# schematic.net
KiCad netlist of a schematic drawn in Altium Designer
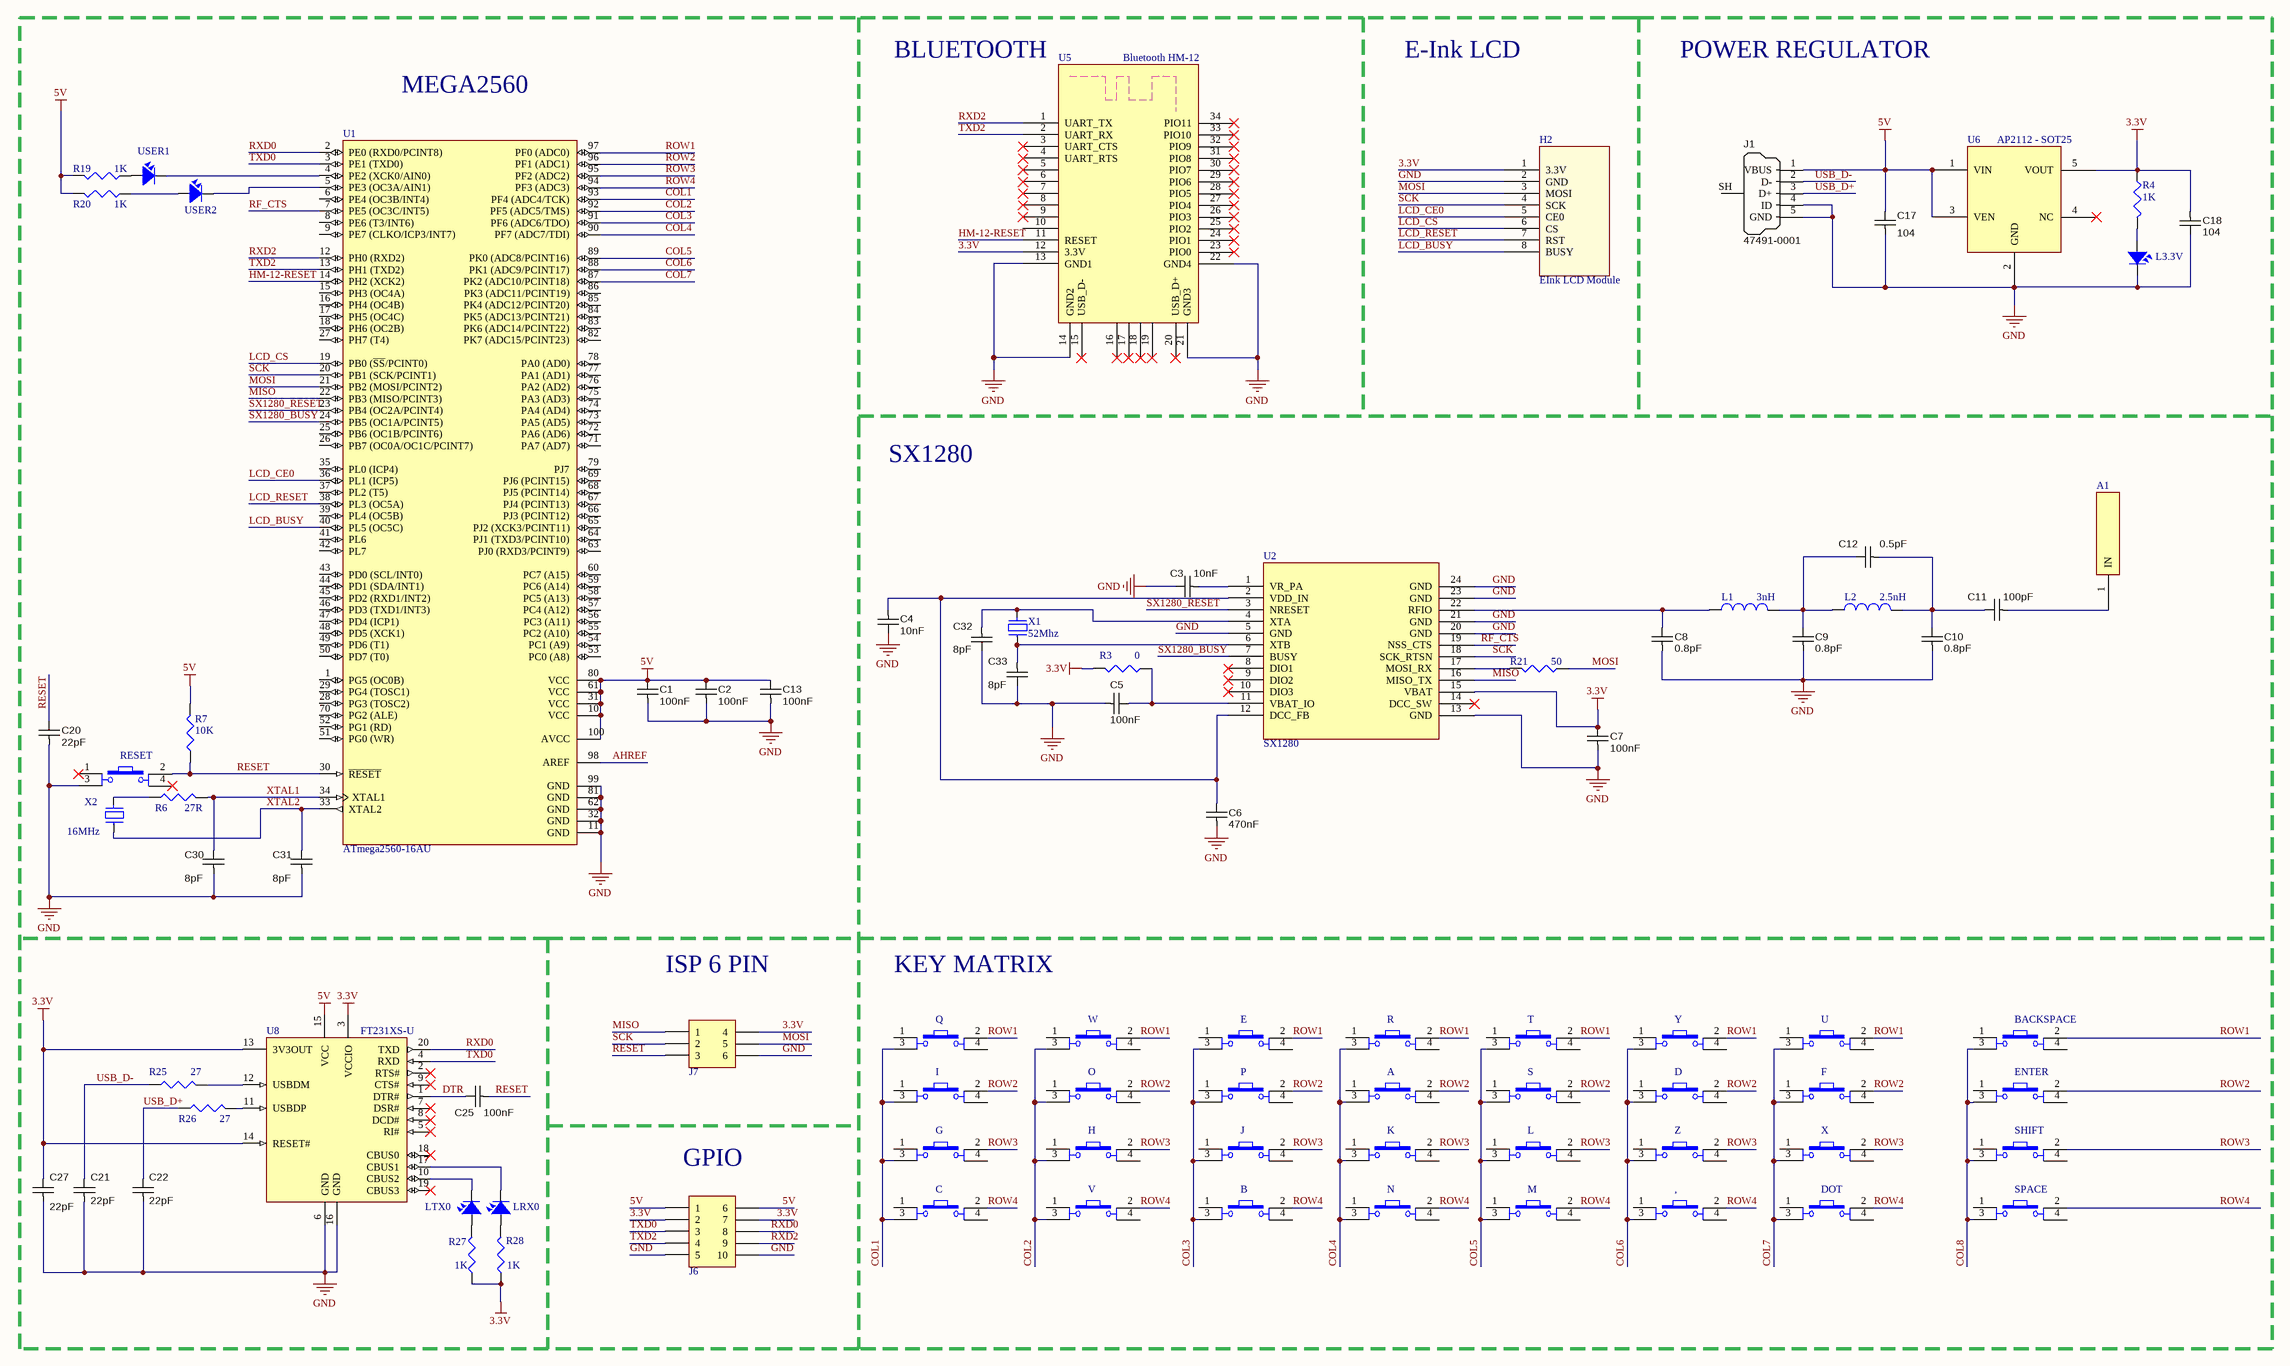
[diagram p0: schematic.SchDoc]

(export (version "E")
  (design (tool "Eeschema 10.0.6"))
  (components
    (comp (ref ",")
      (value "SW")
      (footprint "Kha_Button")
      (description "Switch button 4 pin")
      (libsource (lib "syhaunguyen") (part "SW4"))
    )
    (comp (ref "A")
      (value "SW")
      (footprint "Kha_Button")
      (description "Switch button 4 pin")
      (libsource (lib "syhaunguyen") (part "SW4"))
    )
    (comp (ref "A1")
      (value "Antenna")
      (footprint "Antenna")
      (libsource (lib "EInk_Project_Lib") (part "Antenna"))
    )
    (comp (ref "B")
      (value "SW")
      (footprint "Kha_Button")
      (description "Switch button 4 pin")
      (libsource (lib "syhaunguyen") (part "SW4"))
    )
    (comp (ref "BACKSPACE")
      (value "SW")
      (footprint "Kha_Button")
      (description "Switch button 4 pin")
      (libsource (lib "syhaunguyen") (part "SW4"))
    )
    (comp (ref "C")
      (value "SW")
      (footprint "Kha_Button")
      (description "Switch button 4 pin")
      (libsource (lib "syhaunguyen") (part "SW4"))
    )
    (comp (ref "C1")
      (value "100nF")
      (footprint "SMD-0603c")
      (description "Capacitor SMD Cer 1nF 10% 100V X7R 0603")
      (fields (field (name "TOLERANCE") "±10%") (field (name "Comment") "approved sub OK"))
      (libsource (lib "PBL - Capacitors") (part "CAPC_1n_0603_X7R_100V_10%"))
    )
    (comp (ref "C2")
      (value "100nF")
      (footprint "SMD-0603c")
      (description "Capacitor SMD Cer 1nF 10% 100V X7R 0603")
      (fields (field (name "TOLERANCE") "±10%") (field (name "Comment") "approved sub OK"))
      (libsource (lib "PBL - Capacitors") (part "CAPC_1n_0603_X7R_100V_10%"))
    )
    (comp (ref "C3")
      (value "10nF")
      (footprint "SMD-0603c")
      (description "Capacitor SMD Cer 1nF 10% 100V X7R 0603")
      (fields (field (name "TOLERANCE") "±10%") (field (name "Comment") "approved sub OK"))
      (libsource (lib "PBL - Capacitors") (part "CAPC_1n_0603_X7R_100V_10%"))
    )
    (comp (ref "C4")
      (value "10nF")
      (footprint "SMD-0603c")
      (description "Capacitor SMD Cer 1nF 10% 100V X7R 0603")
      (fields (field (name "TOLERANCE") "±10%") (field (name "Comment") "approved sub OK"))
      (libsource (lib "PBL - Capacitors") (part "CAPC_1n_0603_X7R_100V_10%"))
    )
    (comp (ref "C5")
      (value "100nF")
      (footprint "SMD-0603c")
      (description "Capacitor SMD Cer 1nF 10% 100V X7R 0603")
      (fields (field (name "TOLERANCE") "±10%") (field (name "Comment") "approved sub OK"))
      (libsource (lib "PBL - Capacitors") (part "CAPC_1n_0603_X7R_100V_10%"))
    )
    (comp (ref "C6")
      (value "470nF")
      (footprint "SMD-0603c")
      (description "Capacitor SMD Cer 1nF 10% 100V X7R 0603")
      (fields (field (name "TOLERANCE") "±10%") (field (name "Comment") "approved sub OK"))
      (libsource (lib "PBL - Capacitors") (part "CAPC_1n_0603_X7R_100V_10%"))
    )
    (comp (ref "C7")
      (value "100nF")
      (footprint "SMD-0603c")
      (description "Capacitor SMD Cer 1nF 10% 100V X7R 0603")
      (fields (field (name "TOLERANCE") "±10%") (field (name "Comment") "approved sub OK"))
      (libsource (lib "PBL - Capacitors") (part "CAPC_1n_0603_X7R_100V_10%"))
    )
    (comp (ref "C8")
      (value "0.8pF")
      (footprint "SMD-0603c")
      (description "Capacitor SMD Cer 1nF 10% 100V X7R 0603")
      (fields (field (name "TOLERANCE") "±10%") (field (name "Comment") "approved sub OK"))
      (libsource (lib "PBL - Capacitors") (part "CAPC_1n_0603_X7R_100V_10%"))
    )
    (comp (ref "C9")
      (value "0.8pF")
      (footprint "SMD-0603c")
      (description "Capacitor SMD Cer 1nF 10% 100V X7R 0603")
      (fields (field (name "TOLERANCE") "±10%") (field (name "Comment") "approved sub OK"))
      (libsource (lib "PBL - Capacitors") (part "CAPC_1n_0603_X7R_100V_10%"))
    )
    (comp (ref "C10")
      (value "0.8pF")
      (footprint "SMD-0603c")
      (description "Capacitor SMD Cer 1nF 10% 100V X7R 0603")
      (fields (field (name "TOLERANCE") "±10%") (field (name "Comment") "approved sub OK"))
      (libsource (lib "PBL - Capacitors") (part "CAPC_1n_0603_X7R_100V_10%"))
    )
    (comp (ref "C11")
      (value "100pF")
      (footprint "SMD-0603c")
      (description "Capacitor SMD Cer 1nF 10% 100V X7R 0603")
      (fields (field (name "TOLERANCE") "±10%") (field (name "Comment") "approved sub OK"))
      (libsource (lib "PBL - Capacitors") (part "CAPC_1n_0603_X7R_100V_10%"))
    )
    (comp (ref "C12")
      (value "0.5pF")
      (footprint "SMD-0603c")
      (description "Capacitor SMD Cer 1nF 10% 100V X7R 0603")
      (fields (field (name "TOLERANCE") "±10%") (field (name "Comment") "approved sub OK"))
      (libsource (lib "PBL - Capacitors") (part "CAPC_1n_0603_X7R_100V_10%"))
    )
    (comp (ref "C13")
      (value "100nF")
      (footprint "SMD-0603c")
      (description "Capacitor SMD Cer 1nF 10% 100V X7R 0603")
      (fields (field (name "TOLERANCE") "±10%") (field (name "Comment") "approved sub OK"))
      (libsource (lib "PBL - Capacitors") (part "CAPC_1n_0603_X7R_100V_10%"))
    )
    (comp (ref "C17")
      (value "104")
      (footprint "SMD-0603c")
      (description "Capacitor SMD Cer 1nF 10% 100V X7R 0603")
      (fields (field (name "TOLERANCE") "±10%") (field (name "Comment") "approved sub OK"))
      (libsource (lib "PBL - Capacitors") (part "CAPC_1n_0603_X7R_100V_10%"))
    )
    (comp (ref "C18")
      (value "104")
      (footprint "SMD-0603c")
      (description "Capacitor SMD Cer 1nF 10% 100V X7R 0603")
      (fields (field (name "TOLERANCE") "±10%") (field (name "Comment") "approved sub OK"))
      (libsource (lib "PBL - Capacitors") (part "CAPC_1n_0603_X7R_100V_10%"))
    )
    (comp (ref "C20")
      (value "22pF")
      (footprint "SMD-0603c")
      (description "Capacitor SMD Cer 1nF 10% 100V X7R 0603")
      (fields (field (name "TOLERANCE") "±10%") (field (name "Comment") "approved sub OK"))
      (libsource (lib "PBL - Capacitors") (part "CAPC_1n_0603_X7R_100V_10%"))
    )
    (comp (ref "C21")
      (value "22pF")
      (footprint "SMD-0603c")
      (description "Capacitor SMD Cer 1nF 10% 100V X7R 0603")
      (fields (field (name "TOLERANCE") "±10%") (field (name "Comment") "approved sub OK"))
      (libsource (lib "PBL - Capacitors") (part "CAPC_1n_0603_X7R_100V_10%"))
    )
    (comp (ref "C22")
      (value "22pF")
      (footprint "SMD-0603c")
      (description "Capacitor SMD Cer 1nF 10% 100V X7R 0603")
      (fields (field (name "TOLERANCE") "±10%") (field (name "Comment") "approved sub OK"))
      (libsource (lib "PBL - Capacitors") (part "CAPC_1n_0603_X7R_100V_10%"))
    )
    (comp (ref "C25")
      (value "100nF")
      (footprint "SMD-0603c")
      (description "Capacitor SMD Cer 1nF 10% 100V X7R 0603")
      (fields (field (name "TOLERANCE") "±10%") (field (name "Comment") "approved sub OK"))
      (libsource (lib "PBL - Capacitors") (part "CAPC_1n_0603_X7R_100V_10%"))
    )
    (comp (ref "C27")
      (value "22pF")
      (footprint "SMD-0603c")
      (description "Capacitor SMD Cer 1nF 10% 100V X7R 0603")
      (fields (field (name "TOLERANCE") "±10%") (field (name "Comment") "approved sub OK"))
      (libsource (lib "PBL - Capacitors") (part "CAPC_1n_0603_X7R_100V_10%"))
    )
    (comp (ref "C30")
      (value "8pF")
      (footprint "SMD-0603c")
      (description "Capacitor SMD Cer 1nF 10% 100V X7R 0603")
      (fields (field (name "TOLERANCE") "±10%") (field (name "Comment") "approved sub OK"))
      (libsource (lib "PBL - Capacitors") (part "CAPC_1n_0603_X7R_100V_10%"))
    )
    (comp (ref "C31")
      (value "8pF")
      (footprint "SMD-0603c")
      (description "Capacitor SMD Cer 1nF 10% 100V X7R 0603")
      (fields (field (name "TOLERANCE") "±10%") (field (name "Comment") "approved sub OK"))
      (libsource (lib "PBL - Capacitors") (part "CAPC_1n_0603_X7R_100V_10%"))
    )
    (comp (ref "C32")
      (value "8pF")
      (footprint "SMD-0603c")
      (description "Capacitor SMD Cer 1nF 10% 100V X7R 0603")
      (fields (field (name "TOLERANCE") "±10%") (field (name "Comment") "approved sub OK"))
      (libsource (lib "PBL - Capacitors") (part "CAPC_1n_0603_X7R_100V_10%"))
    )
    (comp (ref "C33")
      (value "8pF")
      (footprint "SMD-0603c")
      (description "Capacitor SMD Cer 1nF 10% 100V X7R 0603")
      (fields (field (name "TOLERANCE") "±10%") (field (name "Comment") "approved sub OK"))
      (libsource (lib "PBL - Capacitors") (part "CAPC_1n_0603_X7R_100V_10%"))
    )
    (comp (ref "D")
      (value "SW")
      (footprint "Kha_Button")
      (description "Switch button 4 pin")
      (libsource (lib "syhaunguyen") (part "SW4"))
    )
    (comp (ref "DOT")
      (value "SW")
      (footprint "Kha_Button")
      (description "Switch button 4 pin")
      (libsource (lib "syhaunguyen") (part "SW4"))
    )
    (comp (ref "E")
      (value "SW")
      (footprint "Kha_Button")
      (description "Switch button 4 pin")
      (libsource (lib "syhaunguyen") (part "SW4"))
    )
    (comp (ref "ENTER")
      (value "SW")
      (footprint "Kha_Button")
      (description "Switch button 4 pin")
      (libsource (lib "syhaunguyen") (part "SW4"))
    )
    (comp (ref "F")
      (value "SW")
      (footprint "Kha_Button")
      (description "Switch button 4 pin")
      (libsource (lib "syhaunguyen") (part "SW4"))
    )
    (comp (ref "G")
      (value "SW")
      (footprint "Kha_Button")
      (description "Switch button 4 pin")
      (libsource (lib "syhaunguyen") (part "SW4"))
    )
    (comp (ref "H")
      (value "SW")
      (footprint "Kha_Button")
      (description "Switch button 4 pin")
      (libsource (lib "syhaunguyen") (part "SW4"))
    )
    (comp (ref "H2")
      (value "EInk LCD Module")
      (footprint "EInk_Module")
      (libsource (lib "EInk_Project_Lib") (part "E-Ink LCD"))
    )
    (comp (ref "I")
      (value "SW")
      (footprint "Kha_Button")
      (description "Switch button 4 pin")
      (libsource (lib "syhaunguyen") (part "SW4"))
    )
    (comp (ref "J")
      (value "SW")
      (footprint "Kha_Button")
      (description "Switch button 4 pin")
      (libsource (lib "syhaunguyen") (part "SW4"))
    )
    (comp (ref "J1")
      (value "USB Micro Type B")
      (footprint "ZIF_CONN_4P_TE84953-4")
      (description "Connector SMD USB Micro Type B middle mount")
      (fields (field (name "MANUFACTURER PART NUMBER 1") "47491-0001"))
      (libsource (lib "PBL - Connectors") (part "USB_Micro_TypeB"))
    )
    (comp (ref "J6")
      (value "10p")
      (footprint "610110249121")
      (description "WR-PHD 2.54 mm Pin Header - SMT Type Double Row Right Angled, 10p")
      (fields (field (name "PARTNUMBER") "610110249121") (field (name "PUBLISHER") "Wurth Elektronik"))
      (libsource (lib "ALTIUM-PHD_2_54_SMT_DOUBLE_ROW_RIGHT_ANGLED_PIN_HEADER_6101XX249121-rev16c") (part "610110249121"))
    )
    (comp (ref "J7")
      (value "06p")
      (footprint "610106249121")
      (description "WR-PHD 2.54 mm Pin Header - SMT Type Double Row Right Angled, 06p")
      (fields (field (name "PARTNUMBER") "610106249121") (field (name "PUBLISHER") "Wurth Elektronik"))
      (libsource (lib "ALTIUM-PHD_2_54_SMT_DOUBLE_ROW_RIGHT_ANGLED_PIN_HEADER_6101XX249121-rev16c") (part "610106249121"))
    )
    (comp (ref "K")
      (value "SW")
      (footprint "Kha_Button")
      (description "Switch button 4 pin")
      (libsource (lib "syhaunguyen") (part "SW4"))
    )
    (comp (ref "L")
      (value "SW")
      (footprint "Kha_Button")
      (description "Switch button 4 pin")
      (libsource (lib "syhaunguyen") (part "SW4"))
    )
    (comp (ref "L1")
      (value "3nH")
      (footprint "0603")
      (description "Inductor")
      (fields (field (name "PUBLISHER") "Altium Limited"))
      (libsource (lib "Miscellaneous Devices") (part "Inductor"))
    )
    (comp (ref "L2")
      (value "2.5nH")
      (footprint "0603")
      (description "Inductor")
      (fields (field (name "PUBLISHER") "Altium Limited"))
      (libsource (lib "Miscellaneous Devices") (part "Inductor"))
    )
    (comp (ref "L3.3V")
      (value "LED SMD")
      (footprint "SM-LED-0805-Blue")
      (libsource (lib "syhaunguyen") (part "LED-SMD-0805"))
    )
    (comp (ref "LRX0")
      (value "LED SMD")
      (footprint "SM-LED-0805-Blue")
      (libsource (lib "syhaunguyen") (part "LED-SMD-0805"))
    )
    (comp (ref "LTX0")
      (value "LED SMD")
      (footprint "SM-LED-0805-Blue")
      (libsource (lib "syhaunguyen") (part "LED-SMD-0805"))
    )
    (comp (ref "M")
      (value "SW")
      (footprint "Kha_Button")
      (description "Switch button 4 pin")
      (libsource (lib "syhaunguyen") (part "SW4"))
    )
    (comp (ref "N")
      (value "SW")
      (footprint "Kha_Button")
      (description "Switch button 4 pin")
      (libsource (lib "syhaunguyen") (part "SW4"))
    )
    (comp (ref "O")
      (value "SW")
      (footprint "Kha_Button")
      (description "Switch button 4 pin")
      (libsource (lib "syhaunguyen") (part "SW4"))
    )
    (comp (ref "P")
      (value "SW")
      (footprint "Kha_Button")
      (description "Switch button 4 pin")
      (libsource (lib "syhaunguyen") (part "SW4"))
    )
    (comp (ref "Q")
      (value "SW")
      (footprint "Kha_Button")
      (description "Switch button 4 pin")
      (libsource (lib "syhaunguyen") (part "SW4"))
    )
    (comp (ref "R")
      (value "SW")
      (footprint "Kha_Button")
      (description "Switch button 4 pin")
      (libsource (lib "syhaunguyen") (part "SW4"))
    )
    (comp (ref "R3")
      (value "0")
      (footprint "J1-0603")
      (description "Resistor")
      (fields (field (name "Comment") "Res3") (field (name "PUBLISHER") "Altium Limited"))
      (libsource (lib "Miscellaneous Devices") (part "Res3"))
    )
    (comp (ref "R4")
      (value "1K")
      (footprint "J1-0603")
      (description "Resistor")
      (fields (field (name "Comment") "Res3") (field (name "PUBLISHER") "Altium Limited"))
      (libsource (lib "Miscellaneous Devices") (part "Res3"))
    )
    (comp (ref "R6")
      (value "27R")
      (footprint "J1-0603")
      (description "Resistor")
      (fields (field (name "Comment") "Res3") (field (name "PUBLISHER") "Altium Limited"))
      (libsource (lib "Miscellaneous Devices") (part "Res3"))
    )
    (comp (ref "R7")
      (value "10K")
      (footprint "J1-0603")
      (description "Resistor")
      (fields (field (name "Comment") "Res3") (field (name "PUBLISHER") "Altium Limited"))
      (libsource (lib "Miscellaneous Devices") (part "Res3"))
    )
    (comp (ref "R19")
      (value "1K")
      (footprint "J1-0603")
      (description "Resistor")
      (fields (field (name "Comment") "Res3") (field (name "PUBLISHER") "Altium Limited"))
      (libsource (lib "Miscellaneous Devices") (part "Res3"))
    )
    (comp (ref "R20")
      (value "1K")
      (footprint "J1-0603")
      (description "Resistor")
      (fields (field (name "Comment") "Res3") (field (name "PUBLISHER") "Altium Limited"))
      (libsource (lib "Miscellaneous Devices") (part "Res3"))
    )
    (comp (ref "R21")
      (value "50")
      (footprint "J1-0603")
      (description "Resistor")
      (fields (field (name "Comment") "Res3") (field (name "PUBLISHER") "Altium Limited"))
      (libsource (lib "Miscellaneous Devices") (part "Res3"))
    )
    (comp (ref "R25")
      (value "27")
      (footprint "J1-0603")
      (description "Resistor")
      (fields (field (name "Comment") "Res3") (field (name "PUBLISHER") "Altium Limited"))
      (libsource (lib "Miscellaneous Devices") (part "Res3"))
    )
    (comp (ref "R26")
      (value "27")
      (footprint "J1-0603")
      (description "Resistor")
      (fields (field (name "Comment") "Res3") (field (name "PUBLISHER") "Altium Limited"))
      (libsource (lib "Miscellaneous Devices") (part "Res3"))
    )
    (comp (ref "R27")
      (value "1K")
      (footprint "J1-0603")
      (description "Resistor")
      (fields (field (name "Comment") "Res3") (field (name "PUBLISHER") "Altium Limited"))
      (libsource (lib "Miscellaneous Devices") (part "Res3"))
    )
    (comp (ref "R28")
      (value "1K")
      (footprint "J1-0603")
      (description "Resistor")
      (fields (field (name "Comment") "Res3") (field (name "PUBLISHER") "Altium Limited"))
      (libsource (lib "Miscellaneous Devices") (part "Res3"))
    )
    (comp (ref "RESET")
      (value "SW")
      (footprint "Kha_Button")
      (description "Switch button 4 pin")
      (libsource (lib "syhaunguyen") (part "SW4"))
    )
    (comp (ref "S")
      (value "SW")
      (footprint "Kha_Button")
      (description "Switch button 4 pin")
      (libsource (lib "syhaunguyen") (part "SW4"))
    )
    (comp (ref "SHIFT")
      (value "SW")
      (footprint "Kha_Button")
      (description "Switch button 4 pin")
      (libsource (lib "syhaunguyen") (part "SW4"))
    )
    (comp (ref "SPACE")
      (value "SW")
      (footprint "Kha_Button")
      (description "Switch button 4 pin")
      (libsource (lib "syhaunguyen") (part "SW4"))
    )
    (comp (ref "T")
      (value "SW")
      (footprint "Kha_Button")
      (description "Switch button 4 pin")
      (libsource (lib "syhaunguyen") (part "SW4"))
    )
    (comp (ref "U")
      (value "SW")
      (footprint "Kha_Button")
      (description "Switch button 4 pin")
      (libsource (lib "syhaunguyen") (part "SW4"))
    )
    (comp (ref "U1")
      (value "ATmega2560-16AU")
      (footprint "100A_N")
      (fields (field (name "PUBLISHER") "Altium Limited"))
      (libsource (lib "Atmel Microcontroller 8-Bit megaAVR") (part "ATmega2560-16AU"))
    )
    (comp (ref "U2")
      (value "SX1280")
      (footprint "SX1280_QFN24 4x4")
      (libsource (lib "EInk_Project_Lib") (part "SX1280"))
    )
    (comp (ref "U5")
      (value "Bluetooth HM-12")
      (footprint "HM-12")
      (libsource (lib "EInk_Project_Lib") (part "HM-12"))
    )
    (comp (ref "U6")
      (value "AP2112 - SOT25")
      (footprint "AP2112 - SOT25")
      (libsource (lib "EInk_Project_Lib") (part "AP2112 - SOT25"))
    )
    (comp (ref "U8")
      (value "FT231XS-U")
      (footprint "SSOP-20_N")
      (fields (field (name "MANUFACTURER") "FTDI"))
      (libsource (lib "FTDI FT-X Series") (part "FT231XS-U"))
    )
    (comp (ref "USER1")
      (value "LED SMD")
      (footprint "SM-LED-0805-Blue")
      (libsource (lib "syhaunguyen") (part "LED-SMD-0805"))
    )
    (comp (ref "USER2")
      (value "LED SMD")
      (footprint "SM-LED-0805-Blue")
      (libsource (lib "syhaunguyen") (part "LED-SMD-0805"))
    )
    (comp (ref "V")
      (value "SW")
      (footprint "Kha_Button")
      (description "Switch button 4 pin")
      (libsource (lib "syhaunguyen") (part "SW4"))
    )
    (comp (ref "W")
      (value "SW")
      (footprint "Kha_Button")
      (description "Switch button 4 pin")
      (libsource (lib "syhaunguyen") (part "SW4"))
    )
    (comp (ref "X")
      (value "SW")
      (footprint "Kha_Button")
      (description "Switch button 4 pin")
      (libsource (lib "syhaunguyen") (part "SW4"))
    )
    (comp (ref "X1")
      (value "52Mhz")
      (footprint "Crystal 52MHz")
      (description "Crystal For all Crystal 2pin.")
      (libsource (lib "syhaunguyen") (part "XT2"))
    )
    (comp (ref "X2")
      (value "16MHz")
      (footprint "PCBComponent_1")
      (description "Crystal For all Crystal 2pin.")
      (libsource (lib "") (part "XT2_1"))
    )
    (comp (ref "Y")
      (value "SW")
      (footprint "Kha_Button")
      (description "Switch button 4 pin")
      (libsource (lib "syhaunguyen") (part "SW4"))
    )
    (comp (ref "Z")
      (value "SW")
      (footprint "Kha_Button")
      (description "Switch button 4 pin")
      (libsource (lib "syhaunguyen") (part "SW4"))
    )
  )
  (nets
    (net (code "1") (name "/AHREF") (class "Default")
      (node (ref "U1") (pin "98") (pinfunction "AREF_98") (pintype "power_in"))
    )
    (net (code "2") (name "/COL1") (class "Default")
      (node (ref "C") (pin "3") (pintype "passive"))
      (node (ref "G") (pin "3") (pintype "passive"))
      (node (ref "I") (pin "3") (pintype "passive"))
      (node (ref "Q") (pin "3") (pintype "passive"))
      (node (ref "U1") (pin "93") (pinfunction "PF4_(ADC4/TCK)_93") (pintype "bidirectional"))
    )
    (net (code "3") (name "/COL2") (class "Default")
      (node (ref "H") (pin "3") (pintype "passive"))
      (node (ref "O") (pin "3") (pintype "passive"))
      (node (ref "U1") (pin "92") (pinfunction "PF5_(ADC5/TMS)_92") (pintype "bidirectional"))
      (node (ref "V") (pin "3") (pintype "passive"))
      (node (ref "W") (pin "3") (pintype "passive"))
    )
    (net (code "4") (name "/COL3") (class "Default")
      (node (ref "B") (pin "3") (pintype "passive"))
      (node (ref "E") (pin "3") (pintype "passive"))
      (node (ref "J") (pin "3") (pintype "passive"))
      (node (ref "P") (pin "3") (pintype "passive"))
      (node (ref "U1") (pin "91") (pinfunction "PF6_(ADC6/TDO)_91") (pintype "bidirectional"))
    )
    (net (code "5") (name "/COL4") (class "Default")
      (node (ref "A") (pin "3") (pintype "passive"))
      (node (ref "K") (pin "3") (pintype "passive"))
      (node (ref "N") (pin "3") (pintype "passive"))
      (node (ref "R") (pin "3") (pintype "passive"))
      (node (ref "U1") (pin "90") (pinfunction "PF7_(ADC7/TDI)_90") (pintype "bidirectional"))
    )
    (net (code "6") (name "/COL5") (class "Default")
      (node (ref "L") (pin "3") (pintype "passive"))
      (node (ref "M") (pin "3") (pintype "passive"))
      (node (ref "S") (pin "3") (pintype "passive"))
      (node (ref "T") (pin "3") (pintype "passive"))
      (node (ref "U1") (pin "89") (pinfunction "PK0_(ADC8/PCINT16)_89") (pintype "bidirectional"))
    )
    (net (code "7") (name "/COL6") (class "Default")
      (node (ref ",") (pin "3") (pintype "passive"))
      (node (ref "D") (pin "3") (pintype "passive"))
      (node (ref "U1") (pin "88") (pinfunction "PK1_(ADC9/PCINT17)_88") (pintype "bidirectional"))
      (node (ref "Y") (pin "3") (pintype "passive"))
      (node (ref "Z") (pin "3") (pintype "passive"))
    )
    (net (code "8") (name "/COL7") (class "Default")
      (node (ref "DOT") (pin "3") (pintype "passive"))
      (node (ref "F") (pin "3") (pintype "passive"))
      (node (ref "U") (pin "3") (pintype "passive"))
      (node (ref "U1") (pin "87") (pinfunction "PK2_(ADC10/PCINT18)_87") (pintype "bidirectional"))
      (node (ref "X") (pin "3") (pintype "passive"))
    )
    (net (code "9") (name "/COL8") (class "Default")
      (node (ref "BACKSPACE") (pin "3") (pintype "passive"))
      (node (ref "ENTER") (pin "3") (pintype "passive"))
      (node (ref "SHIFT") (pin "3") (pintype "passive"))
      (node (ref "SPACE") (pin "3") (pintype "passive"))
    )
    (net (code "10") (name "/DTR") (class "Default")
      (node (ref "C25") (pin "2") (pintype "passive"))
      (node (ref "U8") (pin "1") (pinfunction "DTR#_1") (pintype "output"))
    )
    (net (code "11") (name "/HM-12-RESET") (class "Default")
      (node (ref "U1") (pin "14") (pinfunction "PH2_(XCK2)_14") (pintype "bidirectional"))
      (node (ref "U5") (pin "11") (pinfunction "RESET_11") (pintype "passive"))
    )
    (net (code "12") (name "/LCD_BUSY") (class "Default")
      (node (ref "H2") (pin "8") (pinfunction "BUSY_8") (pintype "passive"))
      (node (ref "U1") (pin "40") (pinfunction "PL5_(OC5C)_40") (pintype "bidirectional"))
    )
    (net (code "13") (name "/LCD_CE0") (class "Default")
      (node (ref "H2") (pin "5") (pinfunction "CE0_5") (pintype "passive"))
      (node (ref "U1") (pin "36") (pinfunction "PL1_(ICP5)_36") (pintype "bidirectional"))
    )
    (net (code "14") (name "/LCD_CS") (class "Default")
      (node (ref "H2") (pin "6") (pinfunction "CS_6") (pintype "passive"))
      (node (ref "U1") (pin "19") (pinfunction "PB0_(~{SS}/PCINT0)_19") (pintype "bidirectional"))
    )
    (net (code "15") (name "/LCD_RESET") (class "Default")
      (node (ref "H2") (pin "7") (pinfunction "RST_7") (pintype "passive"))
      (node (ref "U1") (pin "38") (pinfunction "PL3_(OC5A)_38") (pintype "bidirectional"))
    )
    (net (code "16") (name "/MISO") (class "Default")
      (node (ref "J7") (pin "1") (pinfunction "1_1") (pintype "passive"))
      (node (ref "U1") (pin "22") (pinfunction "PB3_(MISO/PCINT3)_22") (pintype "bidirectional"))
      (node (ref "U2") (pin "16") (pinfunction "MISO_TX_16") (pintype "passive"))
    )
    (net (code "17") (name "/MOSI") (class "Default")
      (node (ref "H2") (pin "3") (pinfunction "MOSI_3") (pintype "passive"))
      (node (ref "J7") (pin "5") (pinfunction "5_5") (pintype "passive"))
      (node (ref "R21") (pin "1") (pinfunction "1_1") (pintype "passive"))
      (node (ref "U1") (pin "21") (pinfunction "PB2_(MOSI/PCINT2)_21") (pintype "bidirectional"))
    )
    (net (code "18") (name "/RESET") (class "Default")
      (node (ref "C20") (pin "2") (pintype "passive"))
      (node (ref "C25") (pin "1") (pintype "passive"))
      (node (ref "J7") (pin "3") (pinfunction "3_3") (pintype "passive"))
      (node (ref "R7") (pin "1") (pinfunction "1_1") (pintype "passive"))
      (node (ref "RESET") (pin "2") (pintype "passive"))
      (node (ref "U1") (pin "30") (pinfunction "~{RESET}_30") (pintype "input"))
    )
    (net (code "19") (name "/RF_CTS") (class "Default")
      (node (ref "U1") (pin "7") (pinfunction "PE5_(OC3C/INT5)_7") (pintype "bidirectional"))
      (node (ref "U2") (pin "19") (pinfunction "NSS_CTS_19") (pintype "passive"))
    )
    (net (code "20") (name "/ROW1") (class "Default")
      (node (ref "BACKSPACE") (pin "2") (pintype "passive"))
      (node (ref "E") (pin "2") (pintype "passive"))
      (node (ref "Q") (pin "2") (pintype "passive"))
      (node (ref "R") (pin "2") (pintype "passive"))
      (node (ref "T") (pin "2") (pintype "passive"))
      (node (ref "U") (pin "2") (pintype "passive"))
      (node (ref "U1") (pin "97") (pinfunction "PF0_(ADC0)_97") (pintype "bidirectional"))
      (node (ref "W") (pin "2") (pintype "passive"))
      (node (ref "Y") (pin "2") (pintype "passive"))
    )
    (net (code "21") (name "/ROW2") (class "Default")
      (node (ref "A") (pin "2") (pintype "passive"))
      (node (ref "D") (pin "2") (pintype "passive"))
      (node (ref "ENTER") (pin "2") (pintype "passive"))
      (node (ref "F") (pin "2") (pintype "passive"))
      (node (ref "I") (pin "2") (pintype "passive"))
      (node (ref "O") (pin "2") (pintype "passive"))
      (node (ref "P") (pin "2") (pintype "passive"))
      (node (ref "S") (pin "2") (pintype "passive"))
      (node (ref "U1") (pin "96") (pinfunction "PF1_(ADC1)_96") (pintype "bidirectional"))
    )
    (net (code "22") (name "/ROW3") (class "Default")
      (node (ref "G") (pin "2") (pintype "passive"))
      (node (ref "H") (pin "2") (pintype "passive"))
      (node (ref "J") (pin "2") (pintype "passive"))
      (node (ref "K") (pin "2") (pintype "passive"))
      (node (ref "L") (pin "2") (pintype "passive"))
      (node (ref "SHIFT") (pin "2") (pintype "passive"))
      (node (ref "U1") (pin "95") (pinfunction "PF2_(ADC2)_95") (pintype "bidirectional"))
      (node (ref "X") (pin "2") (pintype "passive"))
      (node (ref "Z") (pin "2") (pintype "passive"))
    )
    (net (code "23") (name "/ROW4") (class "Default")
      (node (ref ",") (pin "2") (pintype "passive"))
      (node (ref "B") (pin "2") (pintype "passive"))
      (node (ref "C") (pin "2") (pintype "passive"))
      (node (ref "DOT") (pin "2") (pintype "passive"))
      (node (ref "M") (pin "2") (pintype "passive"))
      (node (ref "N") (pin "2") (pintype "passive"))
      (node (ref "SPACE") (pin "2") (pintype "passive"))
      (node (ref "U1") (pin "94") (pinfunction "PF3_(ADC3)_94") (pintype "bidirectional"))
      (node (ref "V") (pin "2") (pintype "passive"))
    )
    (net (code "24") (name "/RXD0") (class "Default")
      (node (ref "J6") (pin "8") (pinfunction "8_8") (pintype "passive"))
      (node (ref "U1") (pin "2") (pinfunction "PE0_(RXD0/PCINT8)_2") (pintype "bidirectional"))
      (node (ref "U8") (pin "20") (pinfunction "TXD_20") (pintype "output"))
    )
    (net (code "25") (name "/RXD2") (class "Default")
      (node (ref "J6") (pin "9") (pinfunction "9_9") (pintype "passive"))
      (node (ref "U1") (pin "12") (pinfunction "PH0_(RXD2)_12") (pintype "bidirectional"))
      (node (ref "U5") (pin "1") (pinfunction "UART_TX_1") (pintype "passive"))
    )
    (net (code "26") (name "/SCK") (class "Default")
      (node (ref "H2") (pin "4") (pinfunction "SCK_4") (pintype "passive"))
      (node (ref "J7") (pin "2") (pinfunction "2_2") (pintype "passive"))
      (node (ref "U1") (pin "20") (pinfunction "PB1_(SCK/PCINT1)_20") (pintype "bidirectional"))
      (node (ref "U2") (pin "18") (pinfunction "SCK_RTSN_18") (pintype "passive"))
    )
    (net (code "27") (name "/SX1280_BUSY") (class "Default")
      (node (ref "U1") (pin "24") (pinfunction "PB5_(OC1A/PCINT5)_24") (pintype "bidirectional"))
      (node (ref "U2") (pin "7") (pinfunction "BUSY_7") (pintype "passive"))
    )
    (net (code "28") (name "/SX1280_RESET") (class "Default")
      (node (ref "U1") (pin "23") (pinfunction "PB4_(OC2A/PCINT4)_23") (pintype "bidirectional"))
      (node (ref "U2") (pin "3") (pinfunction "NRESET_3") (pintype "passive"))
    )
    (net (code "29") (name "/TXD0") (class "Default")
      (node (ref "J6") (pin "3") (pinfunction "3_3") (pintype "passive"))
      (node (ref "U1") (pin "3") (pinfunction "PE1_(TXD0)_3") (pintype "bidirectional"))
      (node (ref "U8") (pin "4") (pinfunction "RXD_4") (pintype "input"))
    )
    (net (code "30") (name "/TXD2") (class "Default")
      (node (ref "J6") (pin "4") (pinfunction "4_4") (pintype "passive"))
      (node (ref "U1") (pin "13") (pinfunction "PH1_(TXD2)_13") (pintype "bidirectional"))
      (node (ref "U5") (pin "2") (pinfunction "UART_RX_2") (pintype "passive"))
    )
    (net (code "31") (name "/USB_D+") (class "Default")
      (node (ref "C22") (pin "2") (pintype "passive"))
      (node (ref "J1") (pin "3") (pinfunction "D+_3") (pintype "passive"))
      (node (ref "R26") (pin "1") (pinfunction "1_1") (pintype "passive"))
    )
    (net (code "32") (name "/USB_D-") (class "Default")
      (node (ref "C21") (pin "2") (pintype "passive"))
      (node (ref "J1") (pin "2") (pinfunction "D-_2") (pintype "passive"))
      (node (ref "R25") (pin "1") (pinfunction "1_1") (pintype "passive"))
    )
    (net (code "33") (name "/XTAL1") (class "Default")
      (node (ref "C30") (pin "2") (pintype "passive"))
      (node (ref "R6") (pin "2") (pinfunction "2_2") (pintype "passive"))
      (node (ref "U1") (pin "34") (pinfunction "XTAL1_34") (pintype "input"))
    )
    (net (code "34") (name "/XTAL2") (class "Default")
      (node (ref "C31") (pin "2") (pintype "passive"))
      (node (ref "U1") (pin "33") (pinfunction "XTAL2_33") (pintype "output"))
      (node (ref "X2") (pin "1") (pinfunction "1_1") (pintype "passive"))
    )
    (net (code "35") (name "3.3V") (class "Default")
      (node (ref "C18") (pin "1") (pintype "passive"))
      (node (ref "C27") (pin "2") (pintype "passive"))
      (node (ref "C7") (pin "2") (pintype "passive"))
      (node (ref "H2") (pin "1") (pinfunction "3.3V_1") (pintype "passive"))
      (node (ref "J6") (pin "2") (pinfunction "2_2") (pintype "passive"))
      (node (ref "J6") (pin "7") (pinfunction "7_7") (pintype "passive"))
      (node (ref "J7") (pin "4") (pinfunction "4_4") (pintype "passive"))
      (node (ref "R27") (pin "1") (pinfunction "1_1") (pintype "passive"))
      (node (ref "R28") (pin "1") (pinfunction "1_1") (pintype "passive"))
      (node (ref "R3") (pin "2") (pinfunction "2_2") (pintype "passive"))
      (node (ref "R4") (pin "1") (pinfunction "1_1") (pintype "passive"))
      (node (ref "U2") (pin "15") (pinfunction "VBAT_15") (pintype "passive"))
      (node (ref "U5") (pin "12") (pinfunction "3.3V_12") (pintype "passive"))
      (node (ref "U6") (pin "5") (pinfunction "VOUT_5") (pintype "passive"))
      (node (ref "U8") (pin "13") (pinfunction "3V3OUT_13") (pintype "power_in"))
      (node (ref "U8") (pin "14") (pinfunction "RESET#_14") (pintype "input"))
      (node (ref "U8") (pin "3") (pinfunction "VCCIO_3") (pintype "power_in"))
    )
    (net (code "36") (name "5V") (class "Default")
      (node (ref "C1") (pin "2") (pintype "passive"))
      (node (ref "C13") (pin "2") (pintype "passive"))
      (node (ref "C17") (pin "2") (pintype "passive"))
      (node (ref "C2") (pin "2") (pintype "passive"))
      (node (ref "J1") (pin "1") (pinfunction "VBUS_1") (pintype "passive"))
      (node (ref "J6") (pin "1") (pinfunction "1_1") (pintype "passive"))
      (node (ref "J6") (pin "6") (pinfunction "6_6") (pintype "passive"))
      (node (ref "R19") (pin "2") (pinfunction "2_2") (pintype "passive"))
      (node (ref "R20") (pin "2") (pinfunction "2_2") (pintype "passive"))
      (node (ref "R7") (pin "2") (pinfunction "2_2") (pintype "passive"))
      (node (ref "U1") (pin "10") (pinfunction "VCC_10") (pintype "power_in"))
      (node (ref "U1") (pin "100") (pinfunction "AVCC_100") (pintype "power_in"))
      (node (ref "U1") (pin "31") (pinfunction "VCC_31") (pintype "power_in"))
      (node (ref "U1") (pin "61") (pinfunction "VCC_61") (pintype "power_in"))
      (node (ref "U1") (pin "80") (pinfunction "VCC_80") (pintype "power_in"))
      (node (ref "U6") (pin "1") (pinfunction "VIN_1") (pintype "passive"))
      (node (ref "U6") (pin "3") (pinfunction "VEN_3") (pintype "passive"))
      (node (ref "U8") (pin "15") (pinfunction "VCC_15") (pintype "power_in"))
    )
    (net (code "37") (name "GND") (class "Default")
      (node (ref "C1") (pin "1") (pintype "passive"))
      (node (ref "C10") (pin "1") (pintype "passive"))
      (node (ref "C13") (pin "1") (pintype "passive"))
      (node (ref "C17") (pin "1") (pintype "passive"))
      (node (ref "C18") (pin "2") (pintype "passive"))
      (node (ref "C2") (pin "1") (pintype "passive"))
      (node (ref "C20") (pin "1") (pintype "passive"))
      (node (ref "C21") (pin "1") (pintype "passive"))
      (node (ref "C22") (pin "1") (pintype "passive"))
      (node (ref "C27") (pin "1") (pintype "passive"))
      (node (ref "C3") (pin "2") (pintype "passive"))
      (node (ref "C30") (pin "1") (pintype "passive"))
      (node (ref "C31") (pin "1") (pintype "passive"))
      (node (ref "C32") (pin "2") (pintype "passive"))
      (node (ref "C33") (pin "2") (pintype "passive"))
      (node (ref "C4") (pin "2") (pintype "passive"))
      (node (ref "C5") (pin "1") (pintype "passive"))
      (node (ref "C6") (pin "1") (pintype "passive"))
      (node (ref "C7") (pin "1") (pintype "passive"))
      (node (ref "C8") (pin "1") (pintype "passive"))
      (node (ref "C9") (pin "1") (pintype "passive"))
      (node (ref "H2") (pin "2") (pinfunction "GND_2") (pintype "passive"))
      (node (ref "J1") (pin "4") (pinfunction "ID_4") (pintype "passive"))
      (node (ref "J1") (pin "5") (pinfunction "GND_5") (pintype "passive"))
      (node (ref "J6") (pin "10") (pinfunction "10_10") (pintype "passive"))
      (node (ref "J6") (pin "5") (pinfunction "5_5") (pintype "passive"))
      (node (ref "J7") (pin "6") (pinfunction "6_6") (pintype "passive"))
      (node (ref "L3.3V") (pin "2") (pinfunction "2_2") (pintype "passive"))
      (node (ref "RESET") (pin "3") (pintype "passive"))
      (node (ref "U1") (pin "11") (pinfunction "GND_11") (pintype "power_in"))
      (node (ref "U1") (pin "32") (pinfunction "GND_32") (pintype "power_in"))
      (node (ref "U1") (pin "62") (pinfunction "GND_62") (pintype "power_in"))
      (node (ref "U1") (pin "81") (pinfunction "GND_81") (pintype "power_in"))
      (node (ref "U1") (pin "99") (pinfunction "GND_99") (pintype "power_in"))
      (node (ref "U2") (pin "13") (pinfunction "GND_13") (pintype "passive"))
      (node (ref "U2") (pin "20") (pinfunction "GND_20") (pintype "passive"))
      (node (ref "U2") (pin "21") (pinfunction "GND_21") (pintype "passive"))
      (node (ref "U2") (pin "23") (pinfunction "GND_23") (pintype "passive"))
      (node (ref "U2") (pin "24") (pinfunction "GND_24") (pintype "passive"))
      (node (ref "U2") (pin "5") (pinfunction "GND_5") (pintype "passive"))
      (node (ref "U5") (pin "13") (pinfunction "GND1_13") (pintype "passive"))
      (node (ref "U5") (pin "14") (pinfunction "GND2_14") (pintype "passive"))
      (node (ref "U5") (pin "21") (pinfunction "GND3_21") (pintype "passive"))
      (node (ref "U5") (pin "22") (pinfunction "GND4_22") (pintype "passive"))
      (node (ref "U6") (pin "2") (pinfunction "GND_2") (pintype "passive"))
      (node (ref "U8") (pin "16") (pinfunction "GND_16") (pintype "power_in"))
      (node (ref "U8") (pin "6") (pinfunction "GND_6") (pintype "power_in"))
    )
    (net (code "38") (name "Net-(A1-IN)") (class "Default")
      (node (ref "A1") (pin "1") (pinfunction "IN_1") (pintype "passive"))
      (node (ref "C11") (pin "1") (pintype "passive"))
    )
    (net (code "39") (name "Net-(C10-Pad2)") (class "Default")
      (node (ref "C10") (pin "2") (pintype "passive"))
      (node (ref "C11") (pin "2") (pintype "passive"))
      (node (ref "C12") (pin "1") (pintype "passive"))
      (node (ref "L2") (pin "2") (pinfunction "2_2") (pintype "passive"))
    )
    (net (code "40") (name "Net-(C12-Pad2)") (class "Default")
      (node (ref "C12") (pin "2") (pintype "passive"))
      (node (ref "C9") (pin "2") (pintype "passive"))
      (node (ref "L1") (pin "2") (pinfunction "2_2") (pintype "passive"))
      (node (ref "L2") (pin "1") (pinfunction "1_1") (pintype "passive"))
    )
    (net (code "41") (name "Net-(L3.3V-Pad1)") (class "Default")
      (node (ref "L3.3V") (pin "1") (pinfunction "1_1") (pintype "passive"))
      (node (ref "R4") (pin "2") (pinfunction "2_2") (pintype "passive"))
    )
    (net (code "42") (name "Net-(LRX0-Pad1)") (class "Default")
      (node (ref "LRX0") (pin "1") (pinfunction "1_1") (pintype "passive"))
      (node (ref "R28") (pin "2") (pinfunction "2_2") (pintype "passive"))
    )
    (net (code "43") (name "Net-(LTX0-Pad1)") (class "Default")
      (node (ref "LTX0") (pin "1") (pinfunction "1_1") (pintype "passive"))
      (node (ref "R27") (pin "2") (pinfunction "2_2") (pintype "passive"))
    )
    (net (code "44") (name "Net-(R6-Pad1)") (class "Default")
      (node (ref "R6") (pin "1") (pinfunction "1_1") (pintype "passive"))
      (node (ref "X2") (pin "2") (pinfunction "2_2") (pintype "passive"))
    )
    (net (code "45") (name "Net-(R19-Pad1)") (class "Default")
      (node (ref "R19") (pin "1") (pinfunction "1_1") (pintype "passive"))
      (node (ref "USER1") (pin "1") (pinfunction "1_1") (pintype "passive"))
    )
    (net (code "46") (name "Net-(R20-Pad1)") (class "Default")
      (node (ref "R20") (pin "1") (pinfunction "1_1") (pintype "passive"))
      (node (ref "USER2") (pin "1") (pinfunction "1_1") (pintype "passive"))
    )
    (net (code "47") (name "Net-(U1-PE2_(XCK0{slash}AIN0))") (class "Default")
      (node (ref "U1") (pin "4") (pinfunction "PE2_(XCK0/AIN0)_4") (pintype "bidirectional"))
      (node (ref "USER1") (pin "2") (pinfunction "2_2") (pintype "passive"))
    )
    (net (code "48") (name "Net-(U1-PE3_(OC3A{slash}AIN1))") (class "Default")
      (node (ref "U1") (pin "5") (pinfunction "PE3_(OC3A/AIN1)_5") (pintype "bidirectional"))
      (node (ref "USER2") (pin "2") (pinfunction "2_2") (pintype "passive"))
    )
    (net (code "49") (name "Net-(U2-DCC_FB)") (class "Default")
      (node (ref "C4") (pin "1") (pintype "passive"))
      (node (ref "C6") (pin "2") (pintype "passive"))
      (node (ref "U2") (pin "12") (pinfunction "DCC_FB_12") (pintype "passive"))
      (node (ref "U2") (pin "2") (pinfunction "VDD_IN_2") (pintype "passive"))
    )
    (net (code "50") (name "Net-(U2-MOSI_RX)") (class "Default")
      (node (ref "R21") (pin "2") (pinfunction "2_2") (pintype "passive"))
      (node (ref "U2") (pin "17") (pinfunction "MOSI_RX_17") (pintype "passive"))
    )
    (net (code "51") (name "Net-(U2-RFIO)") (class "Default")
      (node (ref "C8") (pin "2") (pintype "passive"))
      (node (ref "L1") (pin "1") (pinfunction "1_1") (pintype "passive"))
      (node (ref "U2") (pin "22") (pinfunction "RFIO_22") (pintype "passive"))
    )
    (net (code "52") (name "Net-(U2-VBAT_IO)") (class "Default")
      (node (ref "C5") (pin "2") (pintype "passive"))
      (node (ref "R3") (pin "1") (pinfunction "1_1") (pintype "passive"))
      (node (ref "U2") (pin "11") (pinfunction "VBAT_IO_11") (pintype "passive"))
    )
    (net (code "53") (name "Net-(U2-VR_PA)") (class "Default")
      (node (ref "C3") (pin "1") (pintype "passive"))
      (node (ref "U2") (pin "1") (pinfunction "VR_PA_1") (pintype "passive"))
    )
    (net (code "54") (name "Net-(U2-XTA)") (class "Default")
      (node (ref "C32") (pin "1") (pintype "passive"))
      (node (ref "U2") (pin "4") (pinfunction "XTA_4") (pintype "passive"))
      (node (ref "X1") (pin "3") (pinfunction "2_3") (pintype "passive"))
    )
    (net (code "55") (name "Net-(U2-XTB)") (class "Default")
      (node (ref "C33") (pin "1") (pintype "passive"))
      (node (ref "U2") (pin "6") (pinfunction "XTB_6") (pintype "passive"))
      (node (ref "X1") (pin "1") (pinfunction "1_1") (pintype "passive"))
    )
    (net (code "56") (name "Net-(U8-CBUS1)") (class "Default")
      (node (ref "LRX0") (pin "2") (pinfunction "2_2") (pintype "passive"))
      (node (ref "U8") (pin "17") (pinfunction "CBUS1_17") (pintype "bidirectional"))
    )
    (net (code "57") (name "Net-(U8-CBUS2)") (class "Default")
      (node (ref "LTX0") (pin "2") (pinfunction "2_2") (pintype "passive"))
      (node (ref "U8") (pin "10") (pinfunction "CBUS2_10") (pintype "bidirectional"))
    )
    (net (code "58") (name "Net-(U8-USBDM)") (class "Default")
      (node (ref "R25") (pin "2") (pinfunction "2_2") (pintype "passive"))
      (node (ref "U8") (pin "12") (pinfunction "USBDM_12") (pintype "input"))
    )
    (net (code "59") (name "Net-(U8-USBDP)") (class "Default")
      (node (ref "R26") (pin "2") (pinfunction "2_2") (pintype "passive"))
      (node (ref "U8") (pin "11") (pinfunction "USBDP_11") (pintype "input"))
    )
    (net (code "60") (name "unconnected-(,-Pad1)") (class "Default")
      (node (ref ",") (pin "1") (pintype "passive"))
    )
    (net (code "61") (name "unconnected-(,-Pad4)") (class "Default")
      (node (ref ",") (pin "4") (pintype "passive"))
    )
    (net (code "62") (name "unconnected-(A-Pad1)") (class "Default")
      (node (ref "A") (pin "1") (pintype "passive"))
    )
    (net (code "63") (name "unconnected-(A-Pad4)") (class "Default")
      (node (ref "A") (pin "4") (pintype "passive"))
    )
    (net (code "64") (name "unconnected-(B-Pad1)") (class "Default")
      (node (ref "B") (pin "1") (pintype "passive"))
    )
    (net (code "65") (name "unconnected-(B-Pad4)") (class "Default")
      (node (ref "B") (pin "4") (pintype "passive"))
    )
    (net (code "66") (name "unconnected-(BACKSPACE-Pad1)") (class "Default")
      (node (ref "BACKSPACE") (pin "1") (pintype "passive"))
    )
    (net (code "67") (name "unconnected-(BACKSPACE-Pad4)") (class "Default")
      (node (ref "BACKSPACE") (pin "4") (pintype "passive"))
    )
    (net (code "68") (name "unconnected-(C-Pad1)") (class "Default")
      (node (ref "C") (pin "1") (pintype "passive"))
    )
    (net (code "69") (name "unconnected-(C-Pad4)") (class "Default")
      (node (ref "C") (pin "4") (pintype "passive"))
    )
    (net (code "70") (name "unconnected-(D-Pad1)") (class "Default")
      (node (ref "D") (pin "1") (pintype "passive"))
    )
    (net (code "71") (name "unconnected-(D-Pad4)") (class "Default")
      (node (ref "D") (pin "4") (pintype "passive"))
    )
    (net (code "72") (name "unconnected-(DOT-Pad1)") (class "Default")
      (node (ref "DOT") (pin "1") (pintype "passive"))
    )
    (net (code "73") (name "unconnected-(DOT-Pad4)") (class "Default")
      (node (ref "DOT") (pin "4") (pintype "passive"))
    )
    (net (code "74") (name "unconnected-(E-Pad1)") (class "Default")
      (node (ref "E") (pin "1") (pintype "passive"))
    )
    (net (code "75") (name "unconnected-(E-Pad4)") (class "Default")
      (node (ref "E") (pin "4") (pintype "passive"))
    )
    (net (code "76") (name "unconnected-(ENTER-Pad1)") (class "Default")
      (node (ref "ENTER") (pin "1") (pintype "passive"))
    )
    (net (code "77") (name "unconnected-(ENTER-Pad4)") (class "Default")
      (node (ref "ENTER") (pin "4") (pintype "passive"))
    )
    (net (code "78") (name "unconnected-(F-Pad1)") (class "Default")
      (node (ref "F") (pin "1") (pintype "passive"))
    )
    (net (code "79") (name "unconnected-(F-Pad4)") (class "Default")
      (node (ref "F") (pin "4") (pintype "passive"))
    )
    (net (code "80") (name "unconnected-(G-Pad1)") (class "Default")
      (node (ref "G") (pin "1") (pintype "passive"))
    )
    (net (code "81") (name "unconnected-(G-Pad4)") (class "Default")
      (node (ref "G") (pin "4") (pintype "passive"))
    )
    (net (code "82") (name "unconnected-(H-Pad1)") (class "Default")
      (node (ref "H") (pin "1") (pintype "passive"))
    )
    (net (code "83") (name "unconnected-(H-Pad4)") (class "Default")
      (node (ref "H") (pin "4") (pintype "passive"))
    )
    (net (code "84") (name "unconnected-(I-Pad1)") (class "Default")
      (node (ref "I") (pin "1") (pintype "passive"))
    )
    (net (code "85") (name "unconnected-(I-Pad4)") (class "Default")
      (node (ref "I") (pin "4") (pintype "passive"))
    )
    (net (code "86") (name "unconnected-(J-Pad1)") (class "Default")
      (node (ref "J") (pin "1") (pintype "passive"))
    )
    (net (code "87") (name "unconnected-(J-Pad4)") (class "Default")
      (node (ref "J") (pin "4") (pintype "passive"))
    )
    (net (code "88") (name "unconnected-(J1-Shell-PadSH)") (class "Default")
      (node (ref "J1") (pin "SH") (pinfunction "Shell_SH") (pintype "passive"))
    )
    (net (code "89") (name "unconnected-(K-Pad1)") (class "Default")
      (node (ref "K") (pin "1") (pintype "passive"))
    )
    (net (code "90") (name "unconnected-(K-Pad4)") (class "Default")
      (node (ref "K") (pin "4") (pintype "passive"))
    )
    (net (code "91") (name "unconnected-(L-Pad1)") (class "Default")
      (node (ref "L") (pin "1") (pintype "passive"))
    )
    (net (code "92") (name "unconnected-(L-Pad4)") (class "Default")
      (node (ref "L") (pin "4") (pintype "passive"))
    )
    (net (code "93") (name "unconnected-(M-Pad1)") (class "Default")
      (node (ref "M") (pin "1") (pintype "passive"))
    )
    (net (code "94") (name "unconnected-(M-Pad4)") (class "Default")
      (node (ref "M") (pin "4") (pintype "passive"))
    )
    (net (code "95") (name "unconnected-(N-Pad1)") (class "Default")
      (node (ref "N") (pin "1") (pintype "passive"))
    )
    (net (code "96") (name "unconnected-(N-Pad4)") (class "Default")
      (node (ref "N") (pin "4") (pintype "passive"))
    )
    (net (code "97") (name "unconnected-(O-Pad1)") (class "Default")
      (node (ref "O") (pin "1") (pintype "passive"))
    )
    (net (code "98") (name "unconnected-(O-Pad4)") (class "Default")
      (node (ref "O") (pin "4") (pintype "passive"))
    )
    (net (code "99") (name "unconnected-(P-Pad1)") (class "Default")
      (node (ref "P") (pin "1") (pintype "passive"))
    )
    (net (code "100") (name "unconnected-(P-Pad4)") (class "Default")
      (node (ref "P") (pin "4") (pintype "passive"))
    )
    (net (code "101") (name "unconnected-(Q-Pad1)") (class "Default")
      (node (ref "Q") (pin "1") (pintype "passive"))
    )
    (net (code "102") (name "unconnected-(Q-Pad4)") (class "Default")
      (node (ref "Q") (pin "4") (pintype "passive"))
    )
    (net (code "103") (name "unconnected-(R-Pad1)") (class "Default")
      (node (ref "R") (pin "1") (pintype "passive"))
    )
    (net (code "104") (name "unconnected-(R-Pad4)") (class "Default")
      (node (ref "R") (pin "4") (pintype "passive"))
    )
    (net (code "105") (name "unconnected-(RESET-Pad1)") (class "Default")
      (node (ref "RESET") (pin "1") (pintype "passive+no_connect"))
    )
    (net (code "106") (name "unconnected-(RESET-Pad4)") (class "Default")
      (node (ref "RESET") (pin "4") (pintype "passive+no_connect"))
    )
    (net (code "107") (name "unconnected-(S-Pad1)") (class "Default")
      (node (ref "S") (pin "1") (pintype "passive"))
    )
    (net (code "108") (name "unconnected-(S-Pad4)") (class "Default")
      (node (ref "S") (pin "4") (pintype "passive"))
    )
    (net (code "109") (name "unconnected-(SHIFT-Pad1)") (class "Default")
      (node (ref "SHIFT") (pin "1") (pintype "passive"))
    )
    (net (code "110") (name "unconnected-(SHIFT-Pad4)") (class "Default")
      (node (ref "SHIFT") (pin "4") (pintype "passive"))
    )
    (net (code "111") (name "unconnected-(SPACE-Pad1)") (class "Default")
      (node (ref "SPACE") (pin "1") (pintype "passive"))
    )
    (net (code "112") (name "unconnected-(SPACE-Pad4)") (class "Default")
      (node (ref "SPACE") (pin "4") (pintype "passive"))
    )
    (net (code "113") (name "unconnected-(T-Pad1)") (class "Default")
      (node (ref "T") (pin "1") (pintype "passive"))
    )
    (net (code "114") (name "unconnected-(T-Pad4)") (class "Default")
      (node (ref "T") (pin "4") (pintype "passive"))
    )
    (net (code "115") (name "unconnected-(U-Pad1)") (class "Default")
      (node (ref "U") (pin "1") (pintype "passive"))
    )
    (net (code "116") (name "unconnected-(U-Pad4)") (class "Default")
      (node (ref "U") (pin "4") (pintype "passive"))
    )
    (net (code "117") (name "unconnected-(U1-PA0_(AD0)-Pad78)") (class "Default")
      (node (ref "U1") (pin "78") (pinfunction "PA0_(AD0)_78") (pintype "bidirectional"))
    )
    (net (code "118") (name "unconnected-(U1-PA1_(AD1)-Pad77)") (class "Default")
      (node (ref "U1") (pin "77") (pinfunction "PA1_(AD1)_77") (pintype "bidirectional"))
    )
    (net (code "119") (name "unconnected-(U1-PA2_(AD2)-Pad76)") (class "Default")
      (node (ref "U1") (pin "76") (pinfunction "PA2_(AD2)_76") (pintype "bidirectional"))
    )
    (net (code "120") (name "unconnected-(U1-PA3_(AD3)-Pad75)") (class "Default")
      (node (ref "U1") (pin "75") (pinfunction "PA3_(AD3)_75") (pintype "bidirectional"))
    )
    (net (code "121") (name "unconnected-(U1-PA4_(AD4)-Pad74)") (class "Default")
      (node (ref "U1") (pin "74") (pinfunction "PA4_(AD4)_74") (pintype "bidirectional"))
    )
    (net (code "122") (name "unconnected-(U1-PA5_(AD5)-Pad73)") (class "Default")
      (node (ref "U1") (pin "73") (pinfunction "PA5_(AD5)_73") (pintype "bidirectional"))
    )
    (net (code "123") (name "unconnected-(U1-PA6_(AD6)-Pad72)") (class "Default")
      (node (ref "U1") (pin "72") (pinfunction "PA6_(AD6)_72") (pintype "bidirectional"))
    )
    (net (code "124") (name "unconnected-(U1-PA7_(AD7)-Pad71)") (class "Default")
      (node (ref "U1") (pin "71") (pinfunction "PA7_(AD7)_71") (pintype "bidirectional"))
    )
    (net (code "125") (name "unconnected-(U1-PB6_(OC1B{slash}PCINT6)-Pad25)") (class "Default")
      (node (ref "U1") (pin "25") (pinfunction "PB6_(OC1B/PCINT6)_25") (pintype "bidirectional"))
    )
    (net (code "126") (name "unconnected-(U1-PB7_(OC0A{slash}OC1C{slash}PCINT7)-Pad26)") (class "Default")
      (node (ref "U1") (pin "26") (pinfunction "PB7_(OC0A/OC1C/PCINT7)_26") (pintype "bidirectional"))
    )
    (net (code "127") (name "unconnected-(U1-PC0_(A8)-Pad53)") (class "Default")
      (node (ref "U1") (pin "53") (pinfunction "PC0_(A8)_53") (pintype "bidirectional"))
    )
    (net (code "128") (name "unconnected-(U1-PC1_(A9)-Pad54)") (class "Default")
      (node (ref "U1") (pin "54") (pinfunction "PC1_(A9)_54") (pintype "bidirectional"))
    )
    (net (code "129") (name "unconnected-(U1-PC2_(A10)-Pad55)") (class "Default")
      (node (ref "U1") (pin "55") (pinfunction "PC2_(A10)_55") (pintype "bidirectional"))
    )
    (net (code "130") (name "unconnected-(U1-PC3_(A11)-Pad56)") (class "Default")
      (node (ref "U1") (pin "56") (pinfunction "PC3_(A11)_56") (pintype "bidirectional"))
    )
    (net (code "131") (name "unconnected-(U1-PC4_(A12)-Pad57)") (class "Default")
      (node (ref "U1") (pin "57") (pinfunction "PC4_(A12)_57") (pintype "bidirectional"))
    )
    (net (code "132") (name "unconnected-(U1-PC5_(A13)-Pad58)") (class "Default")
      (node (ref "U1") (pin "58") (pinfunction "PC5_(A13)_58") (pintype "bidirectional"))
    )
    (net (code "133") (name "unconnected-(U1-PC6_(A14)-Pad59)") (class "Default")
      (node (ref "U1") (pin "59") (pinfunction "PC6_(A14)_59") (pintype "bidirectional"))
    )
    (net (code "134") (name "unconnected-(U1-PC7_(A15)-Pad60)") (class "Default")
      (node (ref "U1") (pin "60") (pinfunction "PC7_(A15)_60") (pintype "bidirectional"))
    )
    (net (code "135") (name "unconnected-(U1-PD0_(SCL{slash}INT0)-Pad43)") (class "Default")
      (node (ref "U1") (pin "43") (pinfunction "PD0_(SCL/INT0)_43") (pintype "bidirectional"))
    )
    (net (code "136") (name "unconnected-(U1-PD1_(SDA{slash}INT1)-Pad44)") (class "Default")
      (node (ref "U1") (pin "44") (pinfunction "PD1_(SDA/INT1)_44") (pintype "bidirectional"))
    )
    (net (code "137") (name "unconnected-(U1-PD2_(RXD1{slash}INT2)-Pad45)") (class "Default")
      (node (ref "U1") (pin "45") (pinfunction "PD2_(RXD1/INT2)_45") (pintype "bidirectional"))
    )
    (net (code "138") (name "unconnected-(U1-PD3_(TXD1{slash}INT3)-Pad46)") (class "Default")
      (node (ref "U1") (pin "46") (pinfunction "PD3_(TXD1/INT3)_46") (pintype "bidirectional"))
    )
    (net (code "139") (name "unconnected-(U1-PD4_(ICP1)-Pad47)") (class "Default")
      (node (ref "U1") (pin "47") (pinfunction "PD4_(ICP1)_47") (pintype "bidirectional"))
    )
    (net (code "140") (name "unconnected-(U1-PD5_(XCK1)-Pad48)") (class "Default")
      (node (ref "U1") (pin "48") (pinfunction "PD5_(XCK1)_48") (pintype "bidirectional"))
    )
    (net (code "141") (name "unconnected-(U1-PD6_(T1)-Pad49)") (class "Default")
      (node (ref "U1") (pin "49") (pinfunction "PD6_(T1)_49") (pintype "bidirectional"))
    )
    (net (code "142") (name "unconnected-(U1-PD7_(T0)-Pad50)") (class "Default")
      (node (ref "U1") (pin "50") (pinfunction "PD7_(T0)_50") (pintype "bidirectional"))
    )
    (net (code "143") (name "unconnected-(U1-PE4_(OC3B{slash}INT4)-Pad6)") (class "Default")
      (node (ref "U1") (pin "6") (pinfunction "PE4_(OC3B/INT4)_6") (pintype "bidirectional"))
    )
    (net (code "144") (name "unconnected-(U1-PE6_(T3{slash}INT6)-Pad8)") (class "Default")
      (node (ref "U1") (pin "8") (pinfunction "PE6_(T3/INT6)_8") (pintype "bidirectional"))
    )
    (net (code "145") (name "unconnected-(U1-PE7_(CLKO{slash}ICP3{slash}INT7)-Pad9)") (class "Default")
      (node (ref "U1") (pin "9") (pinfunction "PE7_(CLKO/ICP3/INT7)_9") (pintype "bidirectional"))
    )
    (net (code "146") (name "unconnected-(U1-PG0_(WR)-Pad51)") (class "Default")
      (node (ref "U1") (pin "51") (pinfunction "PG0_(WR)_51") (pintype "bidirectional"))
    )
    (net (code "147") (name "unconnected-(U1-PG1_(RD)-Pad52)") (class "Default")
      (node (ref "U1") (pin "52") (pinfunction "PG1_(RD)_52") (pintype "bidirectional"))
    )
    (net (code "148") (name "unconnected-(U1-PG2_(ALE)-Pad70)") (class "Default")
      (node (ref "U1") (pin "70") (pinfunction "PG2_(ALE)_70") (pintype "bidirectional"))
    )
    (net (code "149") (name "unconnected-(U1-PG3_(TOSC2)-Pad28)") (class "Default")
      (node (ref "U1") (pin "28") (pinfunction "PG3_(TOSC2)_28") (pintype "bidirectional"))
    )
    (net (code "150") (name "unconnected-(U1-PG4_(TOSC1)-Pad29)") (class "Default")
      (node (ref "U1") (pin "29") (pinfunction "PG4_(TOSC1)_29") (pintype "bidirectional"))
    )
    (net (code "151") (name "unconnected-(U1-PG5_(OC0B)-Pad1)") (class "Default")
      (node (ref "U1") (pin "1") (pinfunction "PG5_(OC0B)_1") (pintype "bidirectional"))
    )
    (net (code "152") (name "unconnected-(U1-PH3_(OC4A)-Pad15)") (class "Default")
      (node (ref "U1") (pin "15") (pinfunction "PH3_(OC4A)_15") (pintype "bidirectional"))
    )
    (net (code "153") (name "unconnected-(U1-PH4_(OC4B)-Pad16)") (class "Default")
      (node (ref "U1") (pin "16") (pinfunction "PH4_(OC4B)_16") (pintype "bidirectional"))
    )
    (net (code "154") (name "unconnected-(U1-PH5_(OC4C)-Pad17)") (class "Default")
      (node (ref "U1") (pin "17") (pinfunction "PH5_(OC4C)_17") (pintype "bidirectional"))
    )
    (net (code "155") (name "unconnected-(U1-PH6_(OC2B)-Pad18)") (class "Default")
      (node (ref "U1") (pin "18") (pinfunction "PH6_(OC2B)_18") (pintype "bidirectional"))
    )
    (net (code "156") (name "unconnected-(U1-PH7_(T4)-Pad27)") (class "Default")
      (node (ref "U1") (pin "27") (pinfunction "PH7_(T4)_27") (pintype "bidirectional"))
    )
    (net (code "157") (name "unconnected-(U1-PJ0_(RXD3{slash}PCINT9)-Pad63)") (class "Default")
      (node (ref "U1") (pin "63") (pinfunction "PJ0_(RXD3/PCINT9)_63") (pintype "bidirectional"))
    )
    (net (code "158") (name "unconnected-(U1-PJ1_(TXD3{slash}PCINT10)-Pad64)") (class "Default")
      (node (ref "U1") (pin "64") (pinfunction "PJ1_(TXD3/PCINT10)_64") (pintype "bidirectional"))
    )
    (net (code "159") (name "unconnected-(U1-PJ2_(XCK3{slash}PCINT11)-Pad65)") (class "Default")
      (node (ref "U1") (pin "65") (pinfunction "PJ2_(XCK3/PCINT11)_65") (pintype "bidirectional"))
    )
    (net (code "160") (name "unconnected-(U1-PJ3_(PCINT12)-Pad66)") (class "Default")
      (node (ref "U1") (pin "66") (pinfunction "PJ3_(PCINT12)_66") (pintype "bidirectional"))
    )
    (net (code "161") (name "unconnected-(U1-PJ4_(PCINT13)-Pad67)") (class "Default")
      (node (ref "U1") (pin "67") (pinfunction "PJ4_(PCINT13)_67") (pintype "bidirectional"))
    )
    (net (code "162") (name "unconnected-(U1-PJ5_(PCINT14)-Pad68)") (class "Default")
      (node (ref "U1") (pin "68") (pinfunction "PJ5_(PCINT14)_68") (pintype "bidirectional"))
    )
    (net (code "163") (name "unconnected-(U1-PJ6_(PCINT15)-Pad69)") (class "Default")
      (node (ref "U1") (pin "69") (pinfunction "PJ6_(PCINT15)_69") (pintype "bidirectional"))
    )
    (net (code "164") (name "unconnected-(U1-PJ7-Pad79)") (class "Default")
      (node (ref "U1") (pin "79") (pinfunction "PJ7_79") (pintype "bidirectional"))
    )
    (net (code "165") (name "unconnected-(U1-PK3_(ADC11{slash}PCINT19)-Pad86)") (class "Default")
      (node (ref "U1") (pin "86") (pinfunction "PK3_(ADC11/PCINT19)_86") (pintype "bidirectional"))
    )
    (net (code "166") (name "unconnected-(U1-PK4_(ADC12{slash}PCINT20)-Pad85)") (class "Default")
      (node (ref "U1") (pin "85") (pinfunction "PK4_(ADC12/PCINT20)_85") (pintype "bidirectional"))
    )
    (net (code "167") (name "unconnected-(U1-PK5_(ADC13{slash}PCINT21)-Pad84)") (class "Default")
      (node (ref "U1") (pin "84") (pinfunction "PK5_(ADC13/PCINT21)_84") (pintype "bidirectional"))
    )
    (net (code "168") (name "unconnected-(U1-PK6_(ADC14{slash}PCINT22)-Pad83)") (class "Default")
      (node (ref "U1") (pin "83") (pinfunction "PK6_(ADC14/PCINT22)_83") (pintype "bidirectional"))
    )
    (net (code "169") (name "unconnected-(U1-PK7_(ADC15{slash}PCINT23)-Pad82)") (class "Default")
      (node (ref "U1") (pin "82") (pinfunction "PK7_(ADC15/PCINT23)_82") (pintype "bidirectional"))
    )
    (net (code "170") (name "unconnected-(U1-PL0_(ICP4)-Pad35)") (class "Default")
      (node (ref "U1") (pin "35") (pinfunction "PL0_(ICP4)_35") (pintype "bidirectional"))
    )
    (net (code "171") (name "unconnected-(U1-PL2_(T5)-Pad37)") (class "Default")
      (node (ref "U1") (pin "37") (pinfunction "PL2_(T5)_37") (pintype "bidirectional"))
    )
    (net (code "172") (name "unconnected-(U1-PL4_(OC5B)-Pad39)") (class "Default")
      (node (ref "U1") (pin "39") (pinfunction "PL4_(OC5B)_39") (pintype "bidirectional"))
    )
    (net (code "173") (name "unconnected-(U1-PL6-Pad41)") (class "Default")
      (node (ref "U1") (pin "41") (pinfunction "PL6_41") (pintype "bidirectional"))
    )
    (net (code "174") (name "unconnected-(U1-PL7-Pad42)") (class "Default")
      (node (ref "U1") (pin "42") (pinfunction "PL7_42") (pintype "bidirectional"))
    )
    (net (code "175") (name "unconnected-(U2-DCC_SW-Pad14)") (class "Default")
      (node (ref "U2") (pin "14") (pinfunction "DCC_SW_14") (pintype "passive+no_connect"))
    )
    (net (code "176") (name "unconnected-(U2-DIO1-Pad8)") (class "Default")
      (node (ref "U2") (pin "8") (pinfunction "DIO1_8") (pintype "passive+no_connect"))
    )
    (net (code "177") (name "unconnected-(U2-DIO2-Pad9)") (class "Default")
      (node (ref "U2") (pin "9") (pinfunction "DIO2_9") (pintype "passive+no_connect"))
    )
    (net (code "178") (name "unconnected-(U2-DIO3-Pad10)") (class "Default")
      (node (ref "U2") (pin "10") (pinfunction "DIO3_10") (pintype "passive+no_connect"))
    )
    (net (code "179") (name "unconnected-(U5-PIO0-Pad23)") (class "Default")
      (node (ref "U5") (pin "23") (pinfunction "PIO0_23") (pintype "passive+no_connect"))
    )
    (net (code "180") (name "unconnected-(U5-PIO1-Pad24)") (class "Default")
      (node (ref "U5") (pin "24") (pinfunction "PIO1_24") (pintype "passive+no_connect"))
    )
    (net (code "181") (name "unconnected-(U5-PIO2-Pad25)") (class "Default")
      (node (ref "U5") (pin "25") (pinfunction "PIO2_25") (pintype "passive+no_connect"))
    )
    (net (code "182") (name "unconnected-(U5-PIO3-Pad26)") (class "Default")
      (node (ref "U5") (pin "26") (pinfunction "PIO3_26") (pintype "passive+no_connect"))
    )
    (net (code "183") (name "unconnected-(U5-PIO4-Pad27)") (class "Default")
      (node (ref "U5") (pin "27") (pinfunction "PIO4_27") (pintype "passive+no_connect"))
    )
    (net (code "184") (name "unconnected-(U5-PIO5-Pad28)") (class "Default")
      (node (ref "U5") (pin "28") (pinfunction "PIO5_28") (pintype "passive+no_connect"))
    )
    (net (code "185") (name "unconnected-(U5-PIO6-Pad29)") (class "Default")
      (node (ref "U5") (pin "29") (pinfunction "PIO6_29") (pintype "passive+no_connect"))
    )
    (net (code "186") (name "unconnected-(U5-PIO7-Pad30)") (class "Default")
      (node (ref "U5") (pin "30") (pinfunction "PIO7_30") (pintype "passive+no_connect"))
    )
    (net (code "187") (name "unconnected-(U5-PIO8-Pad31)") (class "Default")
      (node (ref "U5") (pin "31") (pinfunction "PIO8_31") (pintype "passive+no_connect"))
    )
    (net (code "188") (name "unconnected-(U5-PIO9-Pad32)") (class "Default")
      (node (ref "U5") (pin "32") (pinfunction "PIO9_32") (pintype "passive+no_connect"))
    )
    (net (code "189") (name "unconnected-(U5-PIO10-Pad33)") (class "Default")
      (node (ref "U5") (pin "33") (pinfunction "PIO10_33") (pintype "passive+no_connect"))
    )
    (net (code "190") (name "unconnected-(U5-PIO11-Pad34)") (class "Default")
      (node (ref "U5") (pin "34") (pinfunction "PIO11_34") (pintype "passive+no_connect"))
    )
    (net (code "191") (name "unconnected-(U5-Pad5)") (class "Default")
      (node (ref "U5") (pin "5") (pintype "passive+no_connect"))
    )
    (net (code "192") (name "unconnected-(U5-Pad6)") (class "Default")
      (node (ref "U5") (pin "6") (pintype "passive+no_connect"))
    )
    (net (code "193") (name "unconnected-(U5-Pad7)") (class "Default")
      (node (ref "U5") (pin "7") (pintype "passive+no_connect"))
    )
    (net (code "194") (name "unconnected-(U5-Pad8)") (class "Default")
      (node (ref "U5") (pin "8") (pintype "passive+no_connect"))
    )
    (net (code "195") (name "unconnected-(U5-Pad9)") (class "Default")
      (node (ref "U5") (pin "9") (pintype "passive+no_connect"))
    )
    (net (code "196") (name "unconnected-(U5-Pad10)") (class "Default")
      (node (ref "U5") (pin "10") (pintype "passive"))
    )
    (net (code "197") (name "unconnected-(U5-Pad16)") (class "Default")
      (node (ref "U5") (pin "16") (pintype "passive+no_connect"))
    )
    (net (code "198") (name "unconnected-(U5-Pad17)") (class "Default")
      (node (ref "U5") (pin "17") (pintype "passive+no_connect"))
    )
    (net (code "199") (name "unconnected-(U5-Pad18)") (class "Default")
      (node (ref "U5") (pin "18") (pintype "passive+no_connect"))
    )
    (net (code "200") (name "unconnected-(U5-Pad19)") (class "Default")
      (node (ref "U5") (pin "19") (pintype "passive+no_connect"))
    )
    (net (code "201") (name "unconnected-(U5-UART_CTS-Pad3)") (class "Default")
      (node (ref "U5") (pin "3") (pinfunction "UART_CTS_3") (pintype "passive+no_connect"))
    )
    (net (code "202") (name "unconnected-(U5-UART_RTS-Pad4)") (class "Default")
      (node (ref "U5") (pin "4") (pinfunction "UART_RTS_4") (pintype "passive+no_connect"))
    )
    (net (code "203") (name "unconnected-(U5-USB_D+-Pad20)") (class "Default")
      (node (ref "U5") (pin "20") (pinfunction "USB_D+_20") (pintype "passive+no_connect"))
    )
    (net (code "204") (name "unconnected-(U5-USB_D--Pad15)") (class "Default")
      (node (ref "U5") (pin "15") (pinfunction "USB_D-_15") (pintype "passive+no_connect"))
    )
    (net (code "205") (name "unconnected-(U6-NC-Pad4)") (class "Default")
      (node (ref "U6") (pin "4") (pinfunction "NC_4") (pintype "passive+no_connect"))
    )
    (net (code "206") (name "unconnected-(U8-CBUS0-Pad18)") (class "Default")
      (node (ref "U8") (pin "18") (pinfunction "CBUS0_18") (pintype "bidirectional+no_connect"))
    )
    (net (code "207") (name "unconnected-(U8-CBUS3-Pad19)") (class "Default")
      (node (ref "U8") (pin "19") (pinfunction "CBUS3_19") (pintype "bidirectional+no_connect"))
    )
    (net (code "208") (name "unconnected-(U8-CTS#-Pad9)") (class "Default")
      (node (ref "U8") (pin "9") (pinfunction "CTS#_9") (pintype "input+no_connect"))
    )
    (net (code "209") (name "unconnected-(U8-DCD#-Pad8)") (class "Default")
      (node (ref "U8") (pin "8") (pinfunction "DCD#_8") (pintype "input+no_connect"))
    )
    (net (code "210") (name "unconnected-(U8-DSR#-Pad7)") (class "Default")
      (node (ref "U8") (pin "7") (pinfunction "DSR#_7") (pintype "input+no_connect"))
    )
    (net (code "211") (name "unconnected-(U8-RI#-Pad5)") (class "Default")
      (node (ref "U8") (pin "5") (pinfunction "RI#_5") (pintype "input+no_connect"))
    )
    (net (code "212") (name "unconnected-(U8-RTS#-Pad2)") (class "Default")
      (node (ref "U8") (pin "2") (pinfunction "RTS#_2") (pintype "output+no_connect"))
    )
    (net (code "213") (name "unconnected-(V-Pad1)") (class "Default")
      (node (ref "V") (pin "1") (pintype "passive"))
    )
    (net (code "214") (name "unconnected-(V-Pad4)") (class "Default")
      (node (ref "V") (pin "4") (pintype "passive"))
    )
    (net (code "215") (name "unconnected-(W-Pad1)") (class "Default")
      (node (ref "W") (pin "1") (pintype "passive"))
    )
    (net (code "216") (name "unconnected-(W-Pad4)") (class "Default")
      (node (ref "W") (pin "4") (pintype "passive"))
    )
    (net (code "217") (name "unconnected-(X-Pad1)") (class "Default")
      (node (ref "X") (pin "1") (pintype "passive"))
    )
    (net (code "218") (name "unconnected-(X-Pad4)") (class "Default")
      (node (ref "X") (pin "4") (pintype "passive"))
    )
    (net (code "219") (name "unconnected-(Y-Pad1)") (class "Default")
      (node (ref "Y") (pin "1") (pintype "passive"))
    )
    (net (code "220") (name "unconnected-(Y-Pad4)") (class "Default")
      (node (ref "Y") (pin "4") (pintype "passive"))
    )
    (net (code "221") (name "unconnected-(Z-Pad1)") (class "Default")
      (node (ref "Z") (pin "1") (pintype "passive"))
    )
    (net (code "222") (name "unconnected-(Z-Pad4)") (class "Default")
      (node (ref "Z") (pin "4") (pintype "passive"))
    )
  )
)
